# power_monitor.net
KiCad netlist of a schematic drawn in EAGLE
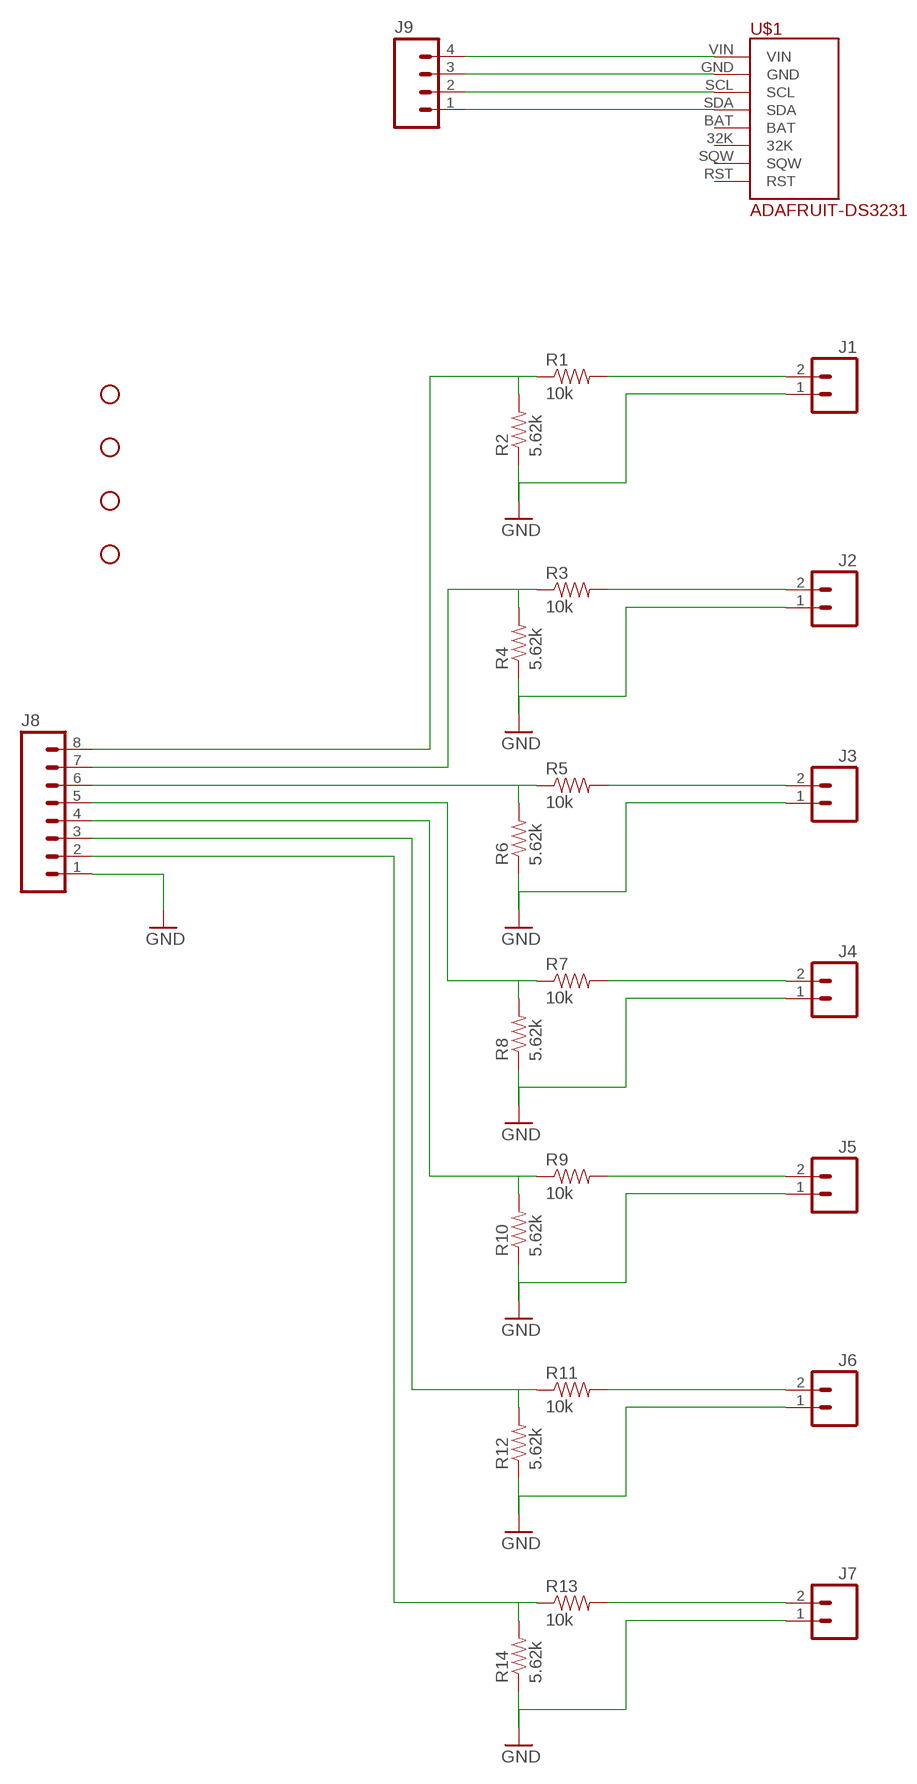
[diagram p0: schematic, sheet 1]

(export (version "E")
  (design (tool "Eeschema 10.0.6"))
  (components
    (comp (ref "H1")
      (value "STAND-OFF")
      (footprint "eagle-import:STAND-OFF")
      (libsource (lib "eagle-import") (part "STAND-OFF"))
    )
    (comp (ref "H2")
      (value "STAND-OFF")
      (footprint "eagle-import:STAND-OFF")
      (libsource (lib "eagle-import") (part "STAND-OFF"))
    )
    (comp (ref "H3")
      (value "STAND-OFF")
      (footprint "eagle-import:STAND-OFF")
      (libsource (lib "eagle-import") (part "STAND-OFF"))
    )
    (comp (ref "H4")
      (value "STAND-OFF")
      (footprint "eagle-import:STAND-OFF")
      (libsource (lib "eagle-import") (part "STAND-OFF"))
    )
    (comp (ref "J1")
      (value "M02LOCK_LONGPADS")
      (footprint "eagle-import:1X02_LOCK_LONGPADS")
      (libsource (lib "eagle-import") (part "M02LOCK_LONGPADS"))
    )
    (comp (ref "J2")
      (value "M02LOCK_LONGPADS")
      (footprint "eagle-import:1X02_LOCK_LONGPADS")
      (libsource (lib "eagle-import") (part "M02LOCK_LONGPADS"))
    )
    (comp (ref "J3")
      (value "M02LOCK_LONGPADS")
      (footprint "eagle-import:1X02_LOCK_LONGPADS")
      (libsource (lib "eagle-import") (part "M02LOCK_LONGPADS"))
    )
    (comp (ref "J4")
      (value "M02LOCK_LONGPADS")
      (footprint "eagle-import:1X02_LOCK_LONGPADS")
      (libsource (lib "eagle-import") (part "M02LOCK_LONGPADS"))
    )
    (comp (ref "J5")
      (value "M02LOCK_LONGPADS")
      (footprint "eagle-import:1X02_LOCK_LONGPADS")
      (libsource (lib "eagle-import") (part "M02LOCK_LONGPADS"))
    )
    (comp (ref "J6")
      (value "M02LOCK_LONGPADS")
      (footprint "eagle-import:1X02_LOCK_LONGPADS")
      (libsource (lib "eagle-import") (part "M02LOCK_LONGPADS"))
    )
    (comp (ref "J7")
      (value "M02LOCK_LONGPADS")
      (footprint "eagle-import:1X02_LOCK_LONGPADS")
      (libsource (lib "eagle-import") (part "M02LOCK_LONGPADS"))
    )
    (comp (ref "J8")
      (value "M08LOCK_LONGPADS")
      (footprint "eagle-import:1X08_LOCK_LONGPADS")
      (libsource (lib "eagle-import") (part "M08LOCK_LONGPADS"))
    )
    (comp (ref "J9")
      (value "M04LOCK_LONGPADS")
      (footprint "eagle-import:1X04_LOCK_LONGPADS")
      (libsource (lib "eagle-import") (part "M04LOCK_LONGPADS"))
    )
    (comp (ref "R1")
      (value "10k")
      (footprint "eagle-import:AXIAL-0.3EZ")
      (libsource (lib "eagle-import") (part "RESISTOREZ"))
    )
    (comp (ref "R2")
      (value "5.62k")
      (footprint "eagle-import:AXIAL-0.3EZ")
      (libsource (lib "eagle-import") (part "RESISTOREZ"))
    )
    (comp (ref "R3")
      (value "10k")
      (footprint "eagle-import:AXIAL-0.3EZ")
      (libsource (lib "eagle-import") (part "RESISTOREZ"))
    )
    (comp (ref "R4")
      (value "5.62k")
      (footprint "eagle-import:AXIAL-0.3EZ")
      (libsource (lib "eagle-import") (part "RESISTOREZ"))
    )
    (comp (ref "R5")
      (value "10k")
      (footprint "eagle-import:AXIAL-0.3EZ")
      (libsource (lib "eagle-import") (part "RESISTOREZ"))
    )
    (comp (ref "R6")
      (value "5.62k")
      (footprint "eagle-import:AXIAL-0.3EZ")
      (libsource (lib "eagle-import") (part "RESISTOREZ"))
    )
    (comp (ref "R7")
      (value "10k")
      (footprint "eagle-import:AXIAL-0.3EZ")
      (libsource (lib "eagle-import") (part "RESISTOREZ"))
    )
    (comp (ref "R8")
      (value "5.62k")
      (footprint "eagle-import:AXIAL-0.3EZ")
      (libsource (lib "eagle-import") (part "RESISTOREZ"))
    )
    (comp (ref "R9")
      (value "10k")
      (footprint "eagle-import:AXIAL-0.3EZ")
      (libsource (lib "eagle-import") (part "RESISTOREZ"))
    )
    (comp (ref "R10")
      (value "5.62k")
      (footprint "eagle-import:AXIAL-0.3EZ")
      (libsource (lib "eagle-import") (part "RESISTOREZ"))
    )
    (comp (ref "R11")
      (value "10k")
      (footprint "eagle-import:AXIAL-0.3EZ")
      (libsource (lib "eagle-import") (part "RESISTOREZ"))
    )
    (comp (ref "R12")
      (value "5.62k")
      (footprint "eagle-import:AXIAL-0.3EZ")
      (libsource (lib "eagle-import") (part "RESISTOREZ"))
    )
    (comp (ref "R13")
      (value "10k")
      (footprint "eagle-import:AXIAL-0.3EZ")
      (libsource (lib "eagle-import") (part "RESISTOREZ"))
    )
    (comp (ref "R14")
      (value "5.62k")
      (footprint "eagle-import:AXIAL-0.3EZ")
      (libsource (lib "eagle-import") (part "RESISTOREZ"))
    )
    (comp (ref "U$1")
      (value "ADAFRUIT-DS3231")
      (footprint "eagle-import:ADAFRUIT-DS3231")
      (libsource (lib "eagle-import") (part "ADAFRUIT-DS3231"))
    )
  )
  (nets
    (net (code "1") (name "GND") (class "Default")
      (node (ref "J1") (pin "1") (pinfunction "1_1") (pintype "passive"))
      (node (ref "J2") (pin "1") (pinfunction "1_1") (pintype "passive"))
      (node (ref "J3") (pin "1") (pinfunction "1_1") (pintype "passive"))
      (node (ref "J4") (pin "1") (pinfunction "1_1") (pintype "passive"))
      (node (ref "J5") (pin "1") (pinfunction "1_1") (pintype "passive"))
      (node (ref "J6") (pin "1") (pinfunction "1_1") (pintype "passive"))
      (node (ref "J7") (pin "1") (pinfunction "1_1") (pintype "passive"))
      (node (ref "J8") (pin "1") (pinfunction "1_1") (pintype "passive"))
      (node (ref "R10") (pin "P$1") (pinfunction "1_P$1") (pintype "passive"))
      (node (ref "R12") (pin "P$1") (pinfunction "1_P$1") (pintype "passive"))
      (node (ref "R14") (pin "P$1") (pinfunction "1_P$1") (pintype "passive"))
      (node (ref "R2") (pin "P$1") (pinfunction "1_P$1") (pintype "passive"))
      (node (ref "R4") (pin "P$1") (pinfunction "1_P$1") (pintype "passive"))
      (node (ref "R6") (pin "P$1") (pinfunction "1_P$1") (pintype "passive"))
      (node (ref "R8") (pin "P$1") (pinfunction "1_P$1") (pintype "passive"))
    )
    (net (code "2") (name "Net-(J9-Pad1)") (class "Default")
      (node (ref "J9") (pin "1") (pinfunction "1_1") (pintype "passive"))
      (node (ref "U$1") (pin "SDA") (pinfunction "SDA_SDA") (pintype "bidirectional"))
    )
    (net (code "3") (name "Net-(J9-Pad2)") (class "Default")
      (node (ref "J9") (pin "2") (pinfunction "2_2") (pintype "passive"))
      (node (ref "U$1") (pin "SCL") (pinfunction "SCL_SCL") (pintype "bidirectional"))
    )
    (net (code "4") (name "Net-(J9-Pad3)") (class "Default")
      (node (ref "J9") (pin "3") (pinfunction "3_3") (pintype "passive"))
      (node (ref "U$1") (pin "GND") (pinfunction "GND_GND") (pintype "bidirectional"))
    )
    (net (code "5") (name "Net-(J9-Pad4)") (class "Default")
      (node (ref "J9") (pin "4") (pinfunction "4_4") (pintype "passive"))
      (node (ref "U$1") (pin "VIN") (pinfunction "VIN_VIN") (pintype "bidirectional"))
    )
    (net (code "6") (name "Net-(R1-1)") (class "Default")
      (node (ref "J8") (pin "8") (pinfunction "8_8") (pintype "passive"))
      (node (ref "R1") (pin "P$1") (pinfunction "1_P$1") (pintype "passive"))
      (node (ref "R2") (pin "P$2") (pinfunction "2_P$2") (pintype "passive"))
    )
    (net (code "7") (name "Net-(R1-2)") (class "Default")
      (node (ref "J1") (pin "2") (pinfunction "2_2") (pintype "passive"))
      (node (ref "R1") (pin "P$2") (pinfunction "2_P$2") (pintype "passive"))
    )
    (net (code "8") (name "Net-(R3-1)") (class "Default")
      (node (ref "J8") (pin "7") (pinfunction "7_7") (pintype "passive"))
      (node (ref "R3") (pin "P$1") (pinfunction "1_P$1") (pintype "passive"))
      (node (ref "R4") (pin "P$2") (pinfunction "2_P$2") (pintype "passive"))
    )
    (net (code "9") (name "Net-(R3-2)") (class "Default")
      (node (ref "J2") (pin "2") (pinfunction "2_2") (pintype "passive"))
      (node (ref "R3") (pin "P$2") (pinfunction "2_P$2") (pintype "passive"))
    )
    (net (code "10") (name "Net-(R5-1)") (class "Default")
      (node (ref "J8") (pin "6") (pinfunction "6_6") (pintype "passive"))
      (node (ref "R5") (pin "P$1") (pinfunction "1_P$1") (pintype "passive"))
      (node (ref "R6") (pin "P$2") (pinfunction "2_P$2") (pintype "passive"))
    )
    (net (code "11") (name "Net-(R5-2)") (class "Default")
      (node (ref "J3") (pin "2") (pinfunction "2_2") (pintype "passive"))
      (node (ref "R5") (pin "P$2") (pinfunction "2_P$2") (pintype "passive"))
    )
    (net (code "12") (name "Net-(R7-1)") (class "Default")
      (node (ref "J8") (pin "5") (pinfunction "5_5") (pintype "passive"))
      (node (ref "R7") (pin "P$1") (pinfunction "1_P$1") (pintype "passive"))
      (node (ref "R8") (pin "P$2") (pinfunction "2_P$2") (pintype "passive"))
    )
    (net (code "13") (name "Net-(R7-2)") (class "Default")
      (node (ref "J4") (pin "2") (pinfunction "2_2") (pintype "passive"))
      (node (ref "R7") (pin "P$2") (pinfunction "2_P$2") (pintype "passive"))
    )
    (net (code "14") (name "Net-(R9-2)") (class "Default")
      (node (ref "J5") (pin "2") (pinfunction "2_2") (pintype "passive"))
      (node (ref "R9") (pin "P$2") (pinfunction "2_P$2") (pintype "passive"))
    )
    (net (code "15") (name "Net-(R10-2)") (class "Default")
      (node (ref "J8") (pin "4") (pinfunction "4_4") (pintype "passive"))
      (node (ref "R10") (pin "P$2") (pinfunction "2_P$2") (pintype "passive"))
      (node (ref "R9") (pin "P$1") (pinfunction "1_P$1") (pintype "passive"))
    )
    (net (code "16") (name "Net-(R11-1)") (class "Default")
      (node (ref "J8") (pin "3") (pinfunction "3_3") (pintype "passive"))
      (node (ref "R11") (pin "P$1") (pinfunction "1_P$1") (pintype "passive"))
      (node (ref "R12") (pin "P$2") (pinfunction "2_P$2") (pintype "passive"))
    )
    (net (code "17") (name "Net-(R11-2)") (class "Default")
      (node (ref "J6") (pin "2") (pinfunction "2_2") (pintype "passive"))
      (node (ref "R11") (pin "P$2") (pinfunction "2_P$2") (pintype "passive"))
    )
    (net (code "18") (name "Net-(R13-1)") (class "Default")
      (node (ref "J8") (pin "2") (pinfunction "2_2") (pintype "passive"))
      (node (ref "R13") (pin "P$1") (pinfunction "1_P$1") (pintype "passive"))
      (node (ref "R14") (pin "P$2") (pinfunction "2_P$2") (pintype "passive"))
    )
    (net (code "19") (name "Net-(R13-2)") (class "Default")
      (node (ref "J7") (pin "2") (pinfunction "2_2") (pintype "passive"))
      (node (ref "R13") (pin "P$2") (pinfunction "2_P$2") (pintype "passive"))
    )
    (net (code "20") (name "unconnected-(U$1-Pad32K)") (class "Default")
      (node (ref "U$1") (pin "32K") (pinfunction "32K_32K") (pintype "bidirectional"))
    )
    (net (code "21") (name "unconnected-(U$1-PadBAT)") (class "Default")
      (node (ref "U$1") (pin "BAT") (pinfunction "BAT_BAT") (pintype "bidirectional"))
    )
    (net (code "22") (name "unconnected-(U$1-PadRST)") (class "Default")
      (node (ref "U$1") (pin "RST") (pinfunction "RST_RST") (pintype "bidirectional"))
    )
    (net (code "23") (name "unconnected-(U$1-PadSQW)") (class "Default")
      (node (ref "U$1") (pin "SQW") (pinfunction "SQW_SQW") (pintype "bidirectional"))
    )
  )
)
